# main_V1_2.net
KiCad netlist of a schematic drawn in EAGLE
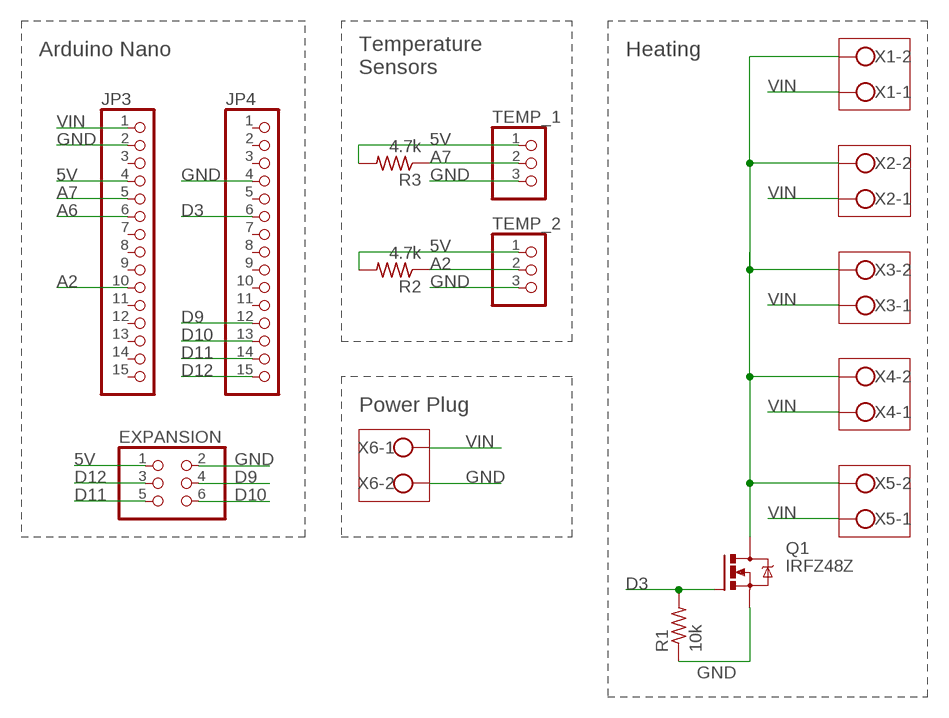
[diagram p0: schematic, sheet 1]

(export (version "E")
  (design (tool "Eeschema 10.0.6"))
  (components
    (comp (ref "EXPANSION")
      (value "PINHD-2X3")
      (footprint "eagle-import:2X03")
      (libsource (lib "eagle-import") (part "PINHD-2X3"))
    )
    (comp (ref "JP3")
      (value "PINHD-1X15-CB")
      (footprint "eagle-import:1X15-CB")
      (libsource (lib "eagle-import") (part "PINHD-1X15-CB"))
    )
    (comp (ref "JP4")
      (value "PINHD-1X15-CB")
      (footprint "eagle-import:1X15-CB")
      (libsource (lib "eagle-import") (part "PINHD-1X15-CB"))
    )
    (comp (ref "Q1")
      (value "IRFZ48Z")
      (footprint "eagle-import:TO220BH")
      (libsource (lib "eagle-import") (part "IRFZ48Z"))
    )
    (comp (ref "R1")
      (value "10k")
      (footprint "eagle-import:0204_7")
      (libsource (lib "eagle-import") (part "R-US_0204/7"))
    )
    (comp (ref "R2")
      (value "4.7k")
      (footprint "eagle-import:0204_7")
      (libsource (lib "eagle-import") (part "R-US_0204/7"))
    )
    (comp (ref "R3")
      (value "4.7k")
      (footprint "eagle-import:0204_7")
      (libsource (lib "eagle-import") (part "R-US_0204/7"))
    )
    (comp (ref "TEMP_1")
      (value "PINHD-1X3")
      (footprint "eagle-import:1X03")
      (libsource (lib "eagle-import") (part "PINHD-1X3"))
    )
    (comp (ref "TEMP_2")
      (value "PINHD-1X3")
      (footprint "eagle-import:1X03")
      (libsource (lib "eagle-import") (part "PINHD-1X3"))
    )
    (comp (ref "X1")
      (value "W237-102")
      (footprint "eagle-import:W237-102")
      (fields (field (name "MPN") "237-102"))
      (libsource (lib "eagle-import") (part "W237-102"))
    )
    (comp (ref "X2")
      (value "W237-102")
      (footprint "eagle-import:W237-102")
      (fields (field (name "MPN") "237-102"))
      (libsource (lib "eagle-import") (part "W237-102"))
    )
    (comp (ref "X3")
      (value "W237-102")
      (footprint "eagle-import:W237-102")
      (fields (field (name "MPN") "237-102"))
      (libsource (lib "eagle-import") (part "W237-102"))
    )
    (comp (ref "X4")
      (value "W237-102")
      (footprint "eagle-import:W237-102")
      (fields (field (name "MPN") "237-102"))
      (libsource (lib "eagle-import") (part "W237-102"))
    )
    (comp (ref "X5")
      (value "W237-102")
      (footprint "eagle-import:W237-102")
      (fields (field (name "MPN") "237-102"))
      (libsource (lib "eagle-import") (part "W237-102"))
    )
    (comp (ref "X6")
      (value "W237-102")
      (footprint "eagle-import:W237-102")
      (fields (field (name "MPN") "237-102"))
      (libsource (lib "eagle-import") (part "W237-102"))
    )
  )
  (nets
    (net (code "1") (name "/5V") (class "Default")
      (node (ref "EXPANSION") (pin "1") (pinfunction "1_1") (pintype "passive"))
      (node (ref "JP3") (pin "4") (pinfunction "4_4") (pintype "passive"))
      (node (ref "R2") (pin "2") (pinfunction "2_2") (pintype "passive"))
      (node (ref "R3") (pin "2") (pinfunction "2_2") (pintype "passive"))
      (node (ref "TEMP_1") (pin "1") (pinfunction "1_1") (pintype "passive"))
      (node (ref "TEMP_2") (pin "1") (pinfunction "1_1") (pintype "passive"))
    )
    (net (code "2") (name "/A2") (class "Default")
      (node (ref "JP3") (pin "10") (pinfunction "10_10") (pintype "passive"))
      (node (ref "R2") (pin "1") (pinfunction "1_1") (pintype "passive"))
      (node (ref "TEMP_2") (pin "2") (pinfunction "2_2") (pintype "passive"))
    )
    (net (code "3") (name "/A6") (class "Default")
      (node (ref "JP3") (pin "6") (pinfunction "6_6") (pintype "passive"))
    )
    (net (code "4") (name "/A7") (class "Default")
      (node (ref "JP3") (pin "5") (pinfunction "5_5") (pintype "passive"))
      (node (ref "R3") (pin "1") (pinfunction "1_1") (pintype "passive"))
      (node (ref "TEMP_1") (pin "2") (pinfunction "2_2") (pintype "passive"))
    )
    (net (code "5") (name "/D3") (class "Default")
      (node (ref "JP4") (pin "6") (pinfunction "6_6") (pintype "passive"))
      (node (ref "Q1") (pin "G") (pinfunction "G_G") (pintype "passive"))
      (node (ref "R1") (pin "2") (pinfunction "2_2") (pintype "passive"))
    )
    (net (code "6") (name "/D9") (class "Default")
      (node (ref "EXPANSION") (pin "4") (pinfunction "4_4") (pintype "passive"))
      (node (ref "JP4") (pin "12") (pinfunction "12_12") (pintype "passive"))
    )
    (net (code "7") (name "/D10") (class "Default")
      (node (ref "EXPANSION") (pin "6") (pinfunction "6_6") (pintype "passive"))
      (node (ref "JP4") (pin "13") (pinfunction "13_13") (pintype "passive"))
    )
    (net (code "8") (name "/D11") (class "Default")
      (node (ref "EXPANSION") (pin "5") (pinfunction "5_5") (pintype "passive"))
      (node (ref "JP4") (pin "14") (pinfunction "14_14") (pintype "passive"))
    )
    (net (code "9") (name "/D12") (class "Default")
      (node (ref "EXPANSION") (pin "3") (pinfunction "3_3") (pintype "passive"))
      (node (ref "JP4") (pin "15") (pinfunction "15_15") (pintype "passive"))
    )
    (net (code "10") (name "/GND") (class "Default")
      (node (ref "EXPANSION") (pin "2") (pinfunction "2_2") (pintype "passive"))
      (node (ref "JP3") (pin "2") (pinfunction "2_2") (pintype "passive"))
      (node (ref "JP4") (pin "4") (pinfunction "4_4") (pintype "passive"))
      (node (ref "Q1") (pin "S") (pinfunction "S_S") (pintype "passive"))
      (node (ref "R1") (pin "1") (pinfunction "1_1") (pintype "passive"))
      (node (ref "TEMP_1") (pin "3") (pinfunction "3_3") (pintype "passive"))
      (node (ref "TEMP_2") (pin "3") (pinfunction "3_3") (pintype "passive"))
      (node (ref "X6") (pin "2") (pinfunction "KL_2") (pintype "passive"))
    )
    (net (code "11") (name "/VIN") (class "Default")
      (node (ref "JP3") (pin "1") (pinfunction "1_1") (pintype "passive"))
      (node (ref "X1") (pin "1") (pinfunction "KL_1") (pintype "passive"))
      (node (ref "X2") (pin "1") (pinfunction "KL_1") (pintype "passive"))
      (node (ref "X3") (pin "1") (pinfunction "KL_1") (pintype "passive"))
      (node (ref "X4") (pin "1") (pinfunction "KL_1") (pintype "passive"))
      (node (ref "X5") (pin "1") (pinfunction "KL_1") (pintype "passive"))
      (node (ref "X6") (pin "1") (pinfunction "KL_1") (pintype "passive"))
    )
    (net (code "12") (name "Net-(X1B-KL)") (class "Default")
      (node (ref "Q1") (pin "D") (pinfunction "D_D") (pintype "passive"))
      (node (ref "X1") (pin "2") (pinfunction "KL_2") (pintype "passive"))
      (node (ref "X2") (pin "2") (pinfunction "KL_2") (pintype "passive"))
      (node (ref "X3") (pin "2") (pinfunction "KL_2") (pintype "passive"))
      (node (ref "X4") (pin "2") (pinfunction "KL_2") (pintype "passive"))
      (node (ref "X5") (pin "2") (pinfunction "KL_2") (pintype "passive"))
    )
    (net (code "13") (name "unconnected-(JP3-Pad3)") (class "Default")
      (node (ref "JP3") (pin "3") (pinfunction "3_3") (pintype "passive"))
    )
    (net (code "14") (name "unconnected-(JP3-Pad7)") (class "Default")
      (node (ref "JP3") (pin "7") (pinfunction "7_7") (pintype "passive"))
    )
    (net (code "15") (name "unconnected-(JP3-Pad8)") (class "Default")
      (node (ref "JP3") (pin "8") (pinfunction "8_8") (pintype "passive"))
    )
    (net (code "16") (name "unconnected-(JP3-Pad9)") (class "Default")
      (node (ref "JP3") (pin "9") (pinfunction "9_9") (pintype "passive"))
    )
    (net (code "17") (name "unconnected-(JP3-Pad11)") (class "Default")
      (node (ref "JP3") (pin "11") (pinfunction "11_11") (pintype "passive"))
    )
    (net (code "18") (name "unconnected-(JP3-Pad12)") (class "Default")
      (node (ref "JP3") (pin "12") (pinfunction "12_12") (pintype "passive"))
    )
    (net (code "19") (name "unconnected-(JP3-Pad13)") (class "Default")
      (node (ref "JP3") (pin "13") (pinfunction "13_13") (pintype "passive"))
    )
    (net (code "20") (name "unconnected-(JP3-Pad14)") (class "Default")
      (node (ref "JP3") (pin "14") (pinfunction "14_14") (pintype "passive"))
    )
    (net (code "21") (name "unconnected-(JP3-Pad15)") (class "Default")
      (node (ref "JP3") (pin "15") (pinfunction "15_15") (pintype "passive"))
    )
    (net (code "22") (name "unconnected-(JP4-Pad1)") (class "Default")
      (node (ref "JP4") (pin "1") (pinfunction "1_1") (pintype "passive"))
    )
    (net (code "23") (name "unconnected-(JP4-Pad2)") (class "Default")
      (node (ref "JP4") (pin "2") (pinfunction "2_2") (pintype "passive"))
    )
    (net (code "24") (name "unconnected-(JP4-Pad3)") (class "Default")
      (node (ref "JP4") (pin "3") (pinfunction "3_3") (pintype "passive"))
    )
    (net (code "25") (name "unconnected-(JP4-Pad5)") (class "Default")
      (node (ref "JP4") (pin "5") (pinfunction "5_5") (pintype "passive"))
    )
    (net (code "26") (name "unconnected-(JP4-Pad7)") (class "Default")
      (node (ref "JP4") (pin "7") (pinfunction "7_7") (pintype "passive"))
    )
    (net (code "27") (name "unconnected-(JP4-Pad8)") (class "Default")
      (node (ref "JP4") (pin "8") (pinfunction "8_8") (pintype "passive"))
    )
    (net (code "28") (name "unconnected-(JP4-Pad9)") (class "Default")
      (node (ref "JP4") (pin "9") (pinfunction "9_9") (pintype "passive"))
    )
    (net (code "29") (name "unconnected-(JP4-Pad10)") (class "Default")
      (node (ref "JP4") (pin "10") (pinfunction "10_10") (pintype "passive"))
    )
    (net (code "30") (name "unconnected-(JP4-Pad11)") (class "Default")
      (node (ref "JP4") (pin "11") (pinfunction "11_11") (pintype "passive"))
    )
  )
)
